# APM32F103VET6.net
KiCad netlist of a schematic drawn in Altium Designer
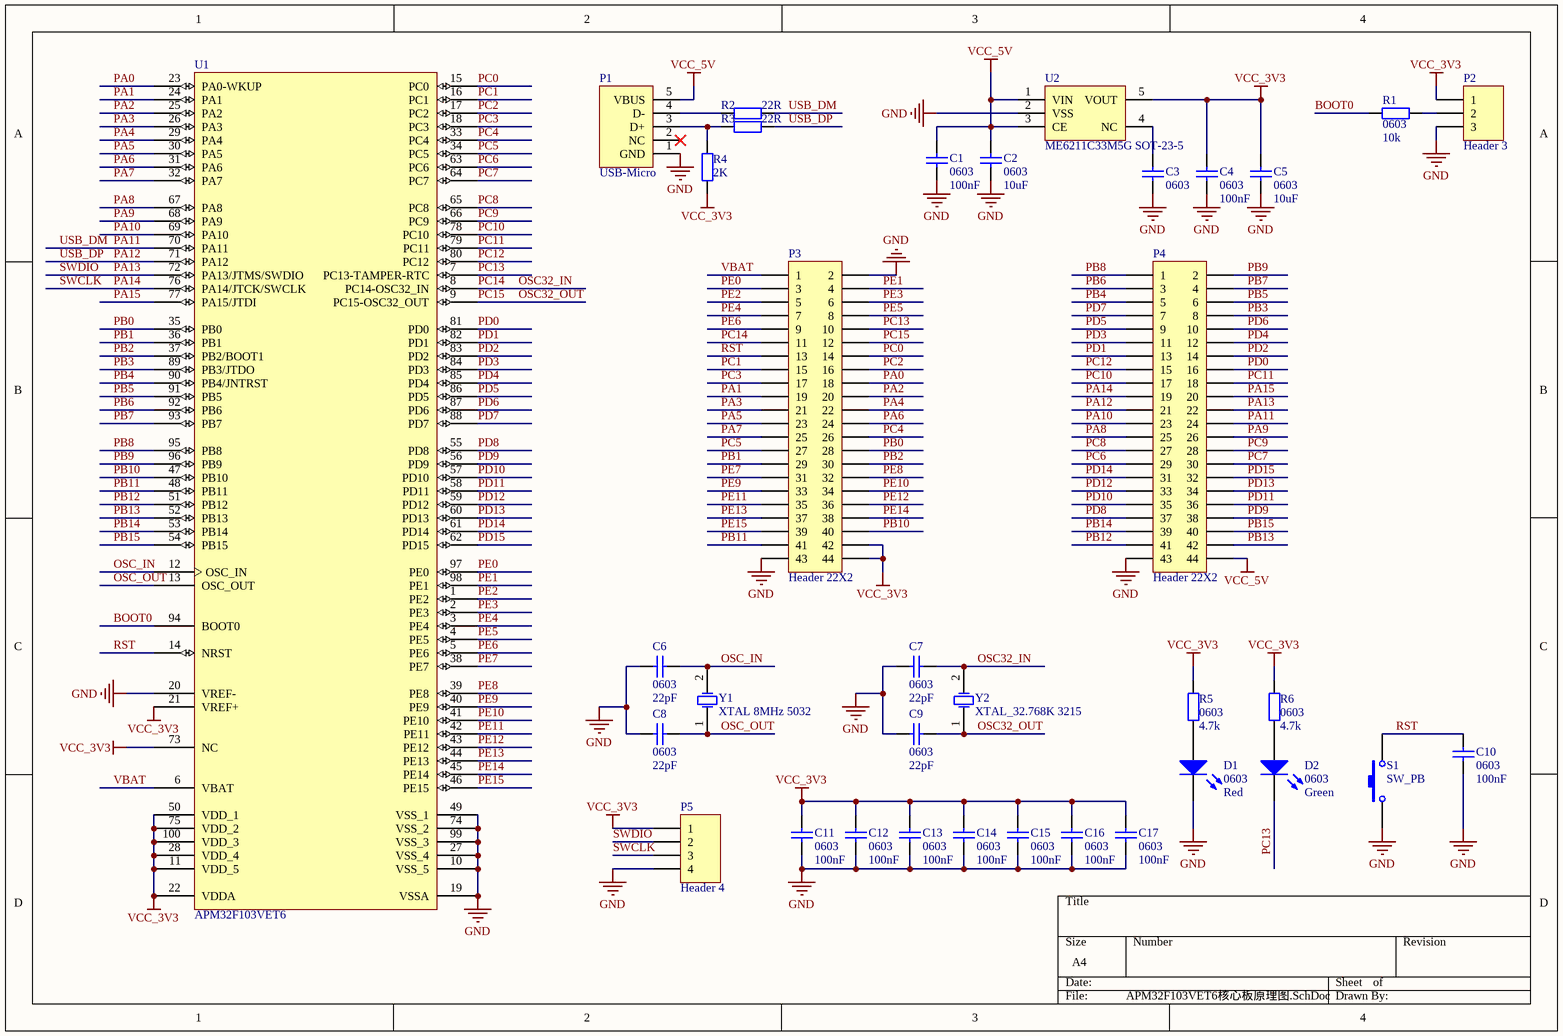
[diagram p0: APM32F103VET6核心板原理图.SchDoc]

(export (version "E")
  (design (tool "Eeschema 10.0.6"))
  (components
    (comp (ref "C1")
      (value "100nF")
      (footprint "0603")
      (description "Capacitor 0603")
      (fields (field (name "Comment") "Cap 0603"))
      (libsource (lib "Schlib1") (part "Cap 0603"))
    )
    (comp (ref "C2")
      (value "10uF")
      (footprint "0603")
      (description "Capacitor 0603")
      (fields (field (name "Comment") "Cap 0603"))
      (libsource (lib "Schlib1") (part "Cap 0603"))
    )
    (comp (ref "C3")
      (value "Cap 0603")
      (footprint "0603")
      (description "Capacitor 0603")
      (libsource (lib "Schlib1") (part "Cap 0603"))
    )
    (comp (ref "C4")
      (value "100nF")
      (footprint "0603")
      (description "Capacitor 0603")
      (fields (field (name "Comment") "Cap 0603"))
      (libsource (lib "Schlib1") (part "Cap 0603"))
    )
    (comp (ref "C5")
      (value "10uF")
      (footprint "0603")
      (description "Capacitor 0603")
      (fields (field (name "Comment") "Cap 0603"))
      (libsource (lib "Schlib1") (part "Cap 0603"))
    )
    (comp (ref "C6")
      (value "22pF")
      (footprint "0603")
      (description "Capacitor 0603")
      (fields (field (name "Comment") "Cap 0603"))
      (libsource (lib "Schlib1") (part "Cap 0603"))
    )
    (comp (ref "C7")
      (value "22pF")
      (footprint "0603")
      (description "Capacitor 0603")
      (fields (field (name "Comment") "Cap 0603"))
      (libsource (lib "Schlib1") (part "Cap 0603"))
    )
    (comp (ref "C8")
      (value "22pF")
      (footprint "0603")
      (description "Capacitor 0603")
      (fields (field (name "Comment") "Cap 0603"))
      (libsource (lib "Schlib1") (part "Cap 0603"))
    )
    (comp (ref "C9")
      (value "22pF")
      (footprint "0603")
      (description "Capacitor 0603")
      (fields (field (name "Comment") "Cap 0603"))
      (libsource (lib "Schlib1") (part "Cap 0603"))
    )
    (comp (ref "C10")
      (value "100nF")
      (footprint "0603")
      (description "Capacitor 0603")
      (fields (field (name "Comment") "Cap 0603"))
      (libsource (lib "Schlib1") (part "Cap 0603"))
    )
    (comp (ref "C11")
      (value "100nF")
      (footprint "0603")
      (description "Capacitor 0603")
      (fields (field (name "Comment") "Cap 0603"))
      (libsource (lib "Schlib1") (part "Cap 0603"))
    )
    (comp (ref "C12")
      (value "100nF")
      (footprint "0603")
      (description "Capacitor 0603")
      (fields (field (name "Comment") "Cap 0603"))
      (libsource (lib "Schlib1") (part "Cap 0603"))
    )
    (comp (ref "C13")
      (value "100nF")
      (footprint "0603")
      (description "Capacitor 0603")
      (fields (field (name "Comment") "Cap 0603"))
      (libsource (lib "Schlib1") (part "Cap 0603"))
    )
    (comp (ref "C14")
      (value "100nF")
      (footprint "0603")
      (description "Capacitor 0603")
      (fields (field (name "Comment") "Cap 0603"))
      (libsource (lib "Schlib1") (part "Cap 0603"))
    )
    (comp (ref "C15")
      (value "100nF")
      (footprint "0603")
      (description "Capacitor 0603")
      (fields (field (name "Comment") "Cap 0603"))
      (libsource (lib "Schlib1") (part "Cap 0603"))
    )
    (comp (ref "C16")
      (value "100nF")
      (footprint "0603")
      (description "Capacitor 0603")
      (fields (field (name "Comment") "Cap 0603"))
      (libsource (lib "Schlib1") (part "Cap 0603"))
    )
    (comp (ref "C17")
      (value "100nF")
      (footprint "0603")
      (description "Capacitor 0603")
      (fields (field (name "Comment") "Cap 0603"))
      (libsource (lib "Schlib1") (part "Cap 0603"))
    )
    (comp (ref "D1")
      (value "Red")
      (footprint "0603")
      (description "LED 0603")
      (libsource (lib "Schlib1") (part "LED 0603"))
    )
    (comp (ref "D2")
      (value "Green")
      (footprint "0603")
      (description "LED 0603")
      (libsource (lib "Schlib1") (part "LED 0603"))
    )
    (comp (ref "P1")
      (value "USB-Micro")
      (footprint "USB Micro")
      (libsource (lib "Schlib1") (part "USB-Micro"))
    )
    (comp (ref "P2")
      (value "Header 3")
      (footprint "HDR1X3")
      (description "Header, 3-Pin")
      (fields (field (name "PUBLISHER") "Altium Limited"))
      (libsource (lib "Miscellaneous Connectors") (part "Header 3"))
    )
    (comp (ref "P3")
      (value "Header 22X2")
      (footprint "HDR2X22")
      (description "Header, 22-Pin, Dual row")
      (fields (field (name "PUBLISHER") "Altium Limited"))
      (libsource (lib "Miscellaneous Connectors") (part "Header 22X2"))
    )
    (comp (ref "P4")
      (value "Header 22X2")
      (footprint "HDR2X22")
      (description "Header, 22-Pin, Dual row")
      (fields (field (name "PUBLISHER") "Altium Limited"))
      (libsource (lib "Miscellaneous Connectors") (part "Header 22X2"))
    )
    (comp (ref "P5")
      (value "Header 4")
      (footprint "HDR1X4")
      (description "Header, 4-Pin")
      (fields (field (name "PUBLISHER") "Altium Limited"))
      (libsource (lib "Miscellaneous Connectors") (part "Header 4"))
    )
    (comp (ref "R1")
      (value "10k")
      (footprint "0603")
      (description "Resistor 0603")
      (fields (field (name "Comment") "Res 0603"))
      (libsource (lib "") (part "Res 0603_1"))
    )
    (comp (ref "R2")
      (value "22R")
      (footprint "R0603-R/C-BY")
      (description "Resistor 0603")
      (fields (field (name "Comment") "Res 0603"))
      (libsource (lib "") (part "Res 0603_1"))
    )
    (comp (ref "R3")
      (value "22R")
      (footprint "R0603-R/C-BY")
      (description "Resistor 0603")
      (fields (field (name "Comment") "Res 0603"))
      (libsource (lib "") (part "Res 0603_1"))
    )
    (comp (ref "R4")
      (value "2K")
      (footprint "R0603-R/C-BY")
      (description "Resistor 0603")
      (fields (field (name "Comment") "Res 0603"))
      (libsource (lib "") (part "Res 0603_2"))
    )
    (comp (ref "R5")
      (value "4.7k")
      (footprint "0603")
      (description "Resistor 0603")
      (fields (field (name "Comment") "Res 0603"))
      (libsource (lib "Schlib1") (part "Res 0603"))
    )
    (comp (ref "R6")
      (value "4.7k")
      (footprint "0603")
      (description "Resistor 0603")
      (fields (field (name "Comment") "Res 0603"))
      (libsource (lib "Schlib1") (part "Res 0603"))
    )
    (comp (ref "S1") (value "SW_PB") (footprint "SW-2Pin") (libsource (lib "Schlib1") (part "SW_PB")))
    (comp (ref "U1")
      (value "APM32F103VET6")
      (footprint "LQFP100_M")
      (description "STM32 ARM-based 32-bit MCU with 64 Kbytes Flash, 100-pin LQFP, Industrial Temperature")
      (fields (field (name "PUBLISHER") "Altium Limited"))
      (libsource (lib "ST Microcontroller 32-Bit STM32") (part "STM32F103VBT6"))
    )
    (comp (ref "U2")
      (value "ME6211C33M5G SOT-23-5")
      (footprint "SOT-23-5")
      (libsource (lib "Schlib1") (part "ME6211C33M5G"))
    )
    (comp (ref "Y1")
      (value "XTAL 8MHz 5032")
      (footprint "XTAL 5032")
      (description "XTAL 8MHZ")
      (libsource (lib "Schlib1") (part "XTAL 8MHZ"))
    )
    (comp (ref "Y2")
      (value "XTAL_32.768K 3215")
      (footprint "XTAL 3215")
      (libsource (lib "Schlib1") (part "XTAL_32.768K 3215"))
    )
  )
  (nets
    (net (code "1") (name "/BOOT0") (class "Default")
      (node (ref "R1") (pin "1") (pinfunction "1_1") (pintype "passive"))
      (node (ref "U1") (pin "94") (pinfunction "BOOT0_94") (pintype "passive"))
    )
    (net (code "2") (name "/OSC32_IN") (class "Default")
      (node (ref "C7") (pin "1") (pinfunction "1_1") (pintype "passive"))
      (node (ref "P3") (pin "11") (pinfunction "11_11") (pintype "passive"))
      (node (ref "U1") (pin "8") (pinfunction "PC14-OSC32_IN_8") (pintype "bidirectional"))
      (node (ref "Y2") (pin "2") (pinfunction "OSC2_2") (pintype "passive"))
    )
    (net (code "3") (name "/OSC32_OUT") (class "Default")
      (node (ref "C9") (pin "1") (pinfunction "1_1") (pintype "passive"))
      (node (ref "P3") (pin "12") (pinfunction "12_12") (pintype "passive"))
      (node (ref "U1") (pin "9") (pinfunction "PC15-OSC32_OUT_9") (pintype "bidirectional"))
      (node (ref "Y2") (pin "1") (pinfunction "OSC1_1") (pintype "passive"))
    )
    (net (code "4") (name "/OSC_IN") (class "Default")
      (node (ref "C6") (pin "1") (pinfunction "1_1") (pintype "passive"))
      (node (ref "U1") (pin "12") (pinfunction "OSC_IN_12") (pintype "passive"))
      (node (ref "Y1") (pin "2") (pinfunction "OSC2_2") (pintype "passive"))
    )
    (net (code "5") (name "/OSC_OUT") (class "Default")
      (node (ref "C8") (pin "1") (pinfunction "1_1") (pintype "passive"))
      (node (ref "U1") (pin "13") (pinfunction "OSC_OUT_13") (pintype "passive"))
      (node (ref "Y1") (pin "1") (pinfunction "OSC1_1") (pintype "passive"))
    )
    (net (code "6") (name "/PA0") (class "Default")
      (node (ref "P3") (pin "18") (pinfunction "18_18") (pintype "passive"))
      (node (ref "U1") (pin "23") (pinfunction "PA0-WKUP_23") (pintype "bidirectional"))
    )
    (net (code "7") (name "/PA1") (class "Default")
      (node (ref "P3") (pin "19") (pinfunction "19_19") (pintype "passive"))
      (node (ref "U1") (pin "24") (pinfunction "PA1_24") (pintype "bidirectional"))
    )
    (net (code "8") (name "/PA2") (class "Default")
      (node (ref "P3") (pin "20") (pinfunction "20_20") (pintype "passive"))
      (node (ref "U1") (pin "25") (pinfunction "PA2_25") (pintype "bidirectional"))
    )
    (net (code "9") (name "/PA3") (class "Default")
      (node (ref "P3") (pin "21") (pinfunction "21_21") (pintype "passive"))
      (node (ref "U1") (pin "26") (pinfunction "PA3_26") (pintype "bidirectional"))
    )
    (net (code "10") (name "/PA4") (class "Default")
      (node (ref "P3") (pin "22") (pinfunction "22_22") (pintype "passive"))
      (node (ref "U1") (pin "29") (pinfunction "PA4_29") (pintype "bidirectional"))
    )
    (net (code "11") (name "/PA5") (class "Default")
      (node (ref "P3") (pin "23") (pinfunction "23_23") (pintype "passive"))
      (node (ref "U1") (pin "30") (pinfunction "PA5_30") (pintype "bidirectional"))
    )
    (net (code "12") (name "/PA6") (class "Default")
      (node (ref "P3") (pin "24") (pinfunction "24_24") (pintype "passive"))
      (node (ref "U1") (pin "31") (pinfunction "PA6_31") (pintype "bidirectional"))
    )
    (net (code "13") (name "/PA7") (class "Default")
      (node (ref "P3") (pin "25") (pinfunction "25_25") (pintype "passive"))
      (node (ref "U1") (pin "32") (pinfunction "PA7_32") (pintype "bidirectional"))
    )
    (net (code "14") (name "/PA8") (class "Default")
      (node (ref "P4") (pin "25") (pinfunction "25_25") (pintype "passive"))
      (node (ref "U1") (pin "67") (pinfunction "PA8_67") (pintype "bidirectional"))
    )
    (net (code "15") (name "/PA9") (class "Default")
      (node (ref "P4") (pin "26") (pinfunction "26_26") (pintype "passive"))
      (node (ref "U1") (pin "68") (pinfunction "PA9_68") (pintype "bidirectional"))
    )
    (net (code "16") (name "/PA10") (class "Default")
      (node (ref "P4") (pin "23") (pinfunction "23_23") (pintype "passive"))
      (node (ref "U1") (pin "69") (pinfunction "PA10_69") (pintype "bidirectional"))
    )
    (net (code "17") (name "/PA11") (class "Default")
      (node (ref "P4") (pin "24") (pinfunction "24_24") (pintype "passive"))
      (node (ref "R2") (pin "2") (pinfunction "2_2") (pintype "passive"))
      (node (ref "U1") (pin "70") (pinfunction "PA11_70") (pintype "bidirectional"))
    )
    (net (code "18") (name "/PA12") (class "Default")
      (node (ref "P4") (pin "21") (pinfunction "21_21") (pintype "passive"))
      (node (ref "R3") (pin "2") (pinfunction "2_2") (pintype "passive"))
      (node (ref "U1") (pin "71") (pinfunction "PA12_71") (pintype "bidirectional"))
    )
    (net (code "19") (name "/PA13") (class "Default")
      (node (ref "P4") (pin "22") (pinfunction "22_22") (pintype "passive"))
      (node (ref "P5") (pin "2") (pinfunction "2_2") (pintype "passive"))
      (node (ref "U1") (pin "72") (pinfunction "PA13/JTMS/SWDIO_72") (pintype "bidirectional"))
    )
    (net (code "20") (name "/PA14") (class "Default")
      (node (ref "P4") (pin "19") (pinfunction "19_19") (pintype "passive"))
      (node (ref "P5") (pin "3") (pinfunction "3_3") (pintype "passive"))
      (node (ref "U1") (pin "76") (pinfunction "PA14/JTCK/SWCLK_76") (pintype "bidirectional"))
    )
    (net (code "21") (name "/PA15") (class "Default")
      (node (ref "P4") (pin "20") (pinfunction "20_20") (pintype "passive"))
      (node (ref "U1") (pin "77") (pinfunction "PA15/JTDI_77") (pintype "bidirectional"))
    )
    (net (code "22") (name "/PB0") (class "Default")
      (node (ref "P3") (pin "28") (pinfunction "28_28") (pintype "passive"))
      (node (ref "U1") (pin "35") (pinfunction "PB0_35") (pintype "bidirectional"))
    )
    (net (code "23") (name "/PB1") (class "Default")
      (node (ref "P3") (pin "29") (pinfunction "29_29") (pintype "passive"))
      (node (ref "U1") (pin "36") (pinfunction "PB1_36") (pintype "bidirectional"))
    )
    (net (code "24") (name "/PB2") (class "Default")
      (node (ref "P3") (pin "30") (pinfunction "30_30") (pintype "passive"))
      (node (ref "U1") (pin "37") (pinfunction "PB2/BOOT1_37") (pintype "bidirectional"))
    )
    (net (code "25") (name "/PB3") (class "Default")
      (node (ref "P4") (pin "8") (pinfunction "8_8") (pintype "passive"))
      (node (ref "U1") (pin "89") (pinfunction "PB3/JTDO_89") (pintype "bidirectional"))
    )
    (net (code "26") (name "/PB4") (class "Default")
      (node (ref "P4") (pin "5") (pinfunction "5_5") (pintype "passive"))
      (node (ref "U1") (pin "90") (pinfunction "PB4/JNTRST_90") (pintype "bidirectional"))
    )
    (net (code "27") (name "/PB5") (class "Default")
      (node (ref "P4") (pin "6") (pinfunction "6_6") (pintype "passive"))
      (node (ref "U1") (pin "91") (pinfunction "PB5_91") (pintype "bidirectional"))
    )
    (net (code "28") (name "/PB6") (class "Default")
      (node (ref "P4") (pin "3") (pinfunction "3_3") (pintype "passive"))
      (node (ref "U1") (pin "92") (pinfunction "PB6_92") (pintype "bidirectional"))
    )
    (net (code "29") (name "/PB7") (class "Default")
      (node (ref "P4") (pin "4") (pinfunction "4_4") (pintype "passive"))
      (node (ref "U1") (pin "93") (pinfunction "PB7_93") (pintype "bidirectional"))
    )
    (net (code "30") (name "/PB8") (class "Default")
      (node (ref "P4") (pin "1") (pinfunction "1_1") (pintype "passive"))
      (node (ref "U1") (pin "95") (pinfunction "PB8_95") (pintype "bidirectional"))
    )
    (net (code "31") (name "/PB9") (class "Default")
      (node (ref "P4") (pin "2") (pinfunction "2_2") (pintype "passive"))
      (node (ref "U1") (pin "96") (pinfunction "PB9_96") (pintype "bidirectional"))
    )
    (net (code "32") (name "/PB10") (class "Default")
      (node (ref "P3") (pin "40") (pinfunction "40_40") (pintype "passive"))
      (node (ref "U1") (pin "47") (pinfunction "PB10_47") (pintype "bidirectional"))
    )
    (net (code "33") (name "/PB11") (class "Default")
      (node (ref "P3") (pin "41") (pinfunction "41_41") (pintype "passive"))
      (node (ref "U1") (pin "48") (pinfunction "PB11_48") (pintype "bidirectional"))
    )
    (net (code "34") (name "/PB12") (class "Default")
      (node (ref "P4") (pin "41") (pinfunction "41_41") (pintype "passive"))
      (node (ref "U1") (pin "51") (pinfunction "PB12_51") (pintype "bidirectional"))
    )
    (net (code "35") (name "/PB13") (class "Default")
      (node (ref "P4") (pin "42") (pinfunction "42_42") (pintype "passive"))
      (node (ref "U1") (pin "52") (pinfunction "PB13_52") (pintype "bidirectional"))
    )
    (net (code "36") (name "/PB14") (class "Default")
      (node (ref "P4") (pin "39") (pinfunction "39_39") (pintype "passive"))
      (node (ref "U1") (pin "53") (pinfunction "PB14_53") (pintype "bidirectional"))
    )
    (net (code "37") (name "/PB15") (class "Default")
      (node (ref "P4") (pin "40") (pinfunction "40_40") (pintype "passive"))
      (node (ref "U1") (pin "54") (pinfunction "PB15_54") (pintype "bidirectional"))
    )
    (net (code "38") (name "/PC0") (class "Default")
      (node (ref "P3") (pin "14") (pinfunction "14_14") (pintype "passive"))
      (node (ref "U1") (pin "15") (pinfunction "PC0_15") (pintype "bidirectional"))
    )
    (net (code "39") (name "/PC1") (class "Default")
      (node (ref "P3") (pin "15") (pinfunction "15_15") (pintype "passive"))
      (node (ref "U1") (pin "16") (pinfunction "PC1_16") (pintype "bidirectional"))
    )
    (net (code "40") (name "/PC2") (class "Default")
      (node (ref "P3") (pin "16") (pinfunction "16_16") (pintype "passive"))
      (node (ref "U1") (pin "17") (pinfunction "PC2_17") (pintype "bidirectional"))
    )
    (net (code "41") (name "/PC3") (class "Default")
      (node (ref "P3") (pin "17") (pinfunction "17_17") (pintype "passive"))
      (node (ref "U1") (pin "18") (pinfunction "PC3_18") (pintype "bidirectional"))
    )
    (net (code "42") (name "/PC4") (class "Default")
      (node (ref "P3") (pin "26") (pinfunction "26_26") (pintype "passive"))
      (node (ref "U1") (pin "33") (pinfunction "PC4_33") (pintype "bidirectional"))
    )
    (net (code "43") (name "/PC5") (class "Default")
      (node (ref "P3") (pin "27") (pinfunction "27_27") (pintype "passive"))
      (node (ref "U1") (pin "34") (pinfunction "PC5_34") (pintype "bidirectional"))
    )
    (net (code "44") (name "/PC6") (class "Default")
      (node (ref "P4") (pin "29") (pinfunction "29_29") (pintype "passive"))
      (node (ref "U1") (pin "63") (pinfunction "PC6_63") (pintype "bidirectional"))
    )
    (net (code "45") (name "/PC7") (class "Default")
      (node (ref "P4") (pin "30") (pinfunction "30_30") (pintype "passive"))
      (node (ref "U1") (pin "64") (pinfunction "PC7_64") (pintype "bidirectional"))
    )
    (net (code "46") (name "/PC8") (class "Default")
      (node (ref "P4") (pin "27") (pinfunction "27_27") (pintype "passive"))
      (node (ref "U1") (pin "65") (pinfunction "PC8_65") (pintype "bidirectional"))
    )
    (net (code "47") (name "/PC9") (class "Default")
      (node (ref "P4") (pin "28") (pinfunction "28_28") (pintype "passive"))
      (node (ref "U1") (pin "66") (pinfunction "PC9_66") (pintype "bidirectional"))
    )
    (net (code "48") (name "/PC10") (class "Default")
      (node (ref "P4") (pin "17") (pinfunction "17_17") (pintype "passive"))
      (node (ref "U1") (pin "78") (pinfunction "PC10_78") (pintype "bidirectional"))
    )
    (net (code "49") (name "/PC11") (class "Default")
      (node (ref "P4") (pin "18") (pinfunction "18_18") (pintype "passive"))
      (node (ref "U1") (pin "79") (pinfunction "PC11_79") (pintype "bidirectional"))
    )
    (net (code "50") (name "/PC12") (class "Default")
      (node (ref "P4") (pin "15") (pinfunction "15_15") (pintype "passive"))
      (node (ref "U1") (pin "80") (pinfunction "PC12_80") (pintype "bidirectional"))
    )
    (net (code "51") (name "/PC13") (class "Default")
      (node (ref "D2") (pin "2") (pinfunction "K_2") (pintype "passive"))
      (node (ref "P3") (pin "10") (pinfunction "10_10") (pintype "passive"))
      (node (ref "U1") (pin "7") (pinfunction "PC13-TAMPER-RTC_7") (pintype "bidirectional"))
    )
    (net (code "52") (name "/PD0") (class "Default")
      (node (ref "P4") (pin "16") (pinfunction "16_16") (pintype "passive"))
      (node (ref "U1") (pin "81") (pinfunction "PD0_81") (pintype "bidirectional"))
    )
    (net (code "53") (name "/PD1") (class "Default")
      (node (ref "P4") (pin "13") (pinfunction "13_13") (pintype "passive"))
      (node (ref "U1") (pin "82") (pinfunction "PD1_82") (pintype "bidirectional"))
    )
    (net (code "54") (name "/PD2") (class "Default")
      (node (ref "P4") (pin "14") (pinfunction "14_14") (pintype "passive"))
      (node (ref "U1") (pin "83") (pinfunction "PD2_83") (pintype "bidirectional"))
    )
    (net (code "55") (name "/PD3") (class "Default")
      (node (ref "P4") (pin "11") (pinfunction "11_11") (pintype "passive"))
      (node (ref "U1") (pin "84") (pinfunction "PD3_84") (pintype "bidirectional"))
    )
    (net (code "56") (name "/PD4") (class "Default")
      (node (ref "P4") (pin "12") (pinfunction "12_12") (pintype "passive"))
      (node (ref "U1") (pin "85") (pinfunction "PD4_85") (pintype "bidirectional"))
    )
    (net (code "57") (name "/PD5") (class "Default")
      (node (ref "P4") (pin "9") (pinfunction "9_9") (pintype "passive"))
      (node (ref "U1") (pin "86") (pinfunction "PD5_86") (pintype "bidirectional"))
    )
    (net (code "58") (name "/PD6") (class "Default")
      (node (ref "P4") (pin "10") (pinfunction "10_10") (pintype "passive"))
      (node (ref "U1") (pin "87") (pinfunction "PD6_87") (pintype "bidirectional"))
    )
    (net (code "59") (name "/PD7") (class "Default")
      (node (ref "P4") (pin "7") (pinfunction "7_7") (pintype "passive"))
      (node (ref "U1") (pin "88") (pinfunction "PD7_88") (pintype "bidirectional"))
    )
    (net (code "60") (name "/PD8") (class "Default")
      (node (ref "P4") (pin "37") (pinfunction "37_37") (pintype "passive"))
      (node (ref "U1") (pin "55") (pinfunction "PD8_55") (pintype "bidirectional"))
    )
    (net (code "61") (name "/PD9") (class "Default")
      (node (ref "P4") (pin "38") (pinfunction "38_38") (pintype "passive"))
      (node (ref "U1") (pin "56") (pinfunction "PD9_56") (pintype "bidirectional"))
    )
    (net (code "62") (name "/PD10") (class "Default")
      (node (ref "P4") (pin "35") (pinfunction "35_35") (pintype "passive"))
      (node (ref "U1") (pin "57") (pinfunction "PD10_57") (pintype "bidirectional"))
    )
    (net (code "63") (name "/PD11") (class "Default")
      (node (ref "P4") (pin "36") (pinfunction "36_36") (pintype "passive"))
      (node (ref "U1") (pin "58") (pinfunction "PD11_58") (pintype "bidirectional"))
    )
    (net (code "64") (name "/PD12") (class "Default")
      (node (ref "P4") (pin "33") (pinfunction "33_33") (pintype "passive"))
      (node (ref "U1") (pin "59") (pinfunction "PD12_59") (pintype "bidirectional"))
    )
    (net (code "65") (name "/PD13") (class "Default")
      (node (ref "P4") (pin "34") (pinfunction "34_34") (pintype "passive"))
      (node (ref "U1") (pin "60") (pinfunction "PD13_60") (pintype "bidirectional"))
    )
    (net (code "66") (name "/PD14") (class "Default")
      (node (ref "P4") (pin "31") (pinfunction "31_31") (pintype "passive"))
      (node (ref "U1") (pin "61") (pinfunction "PD14_61") (pintype "bidirectional"))
    )
    (net (code "67") (name "/PD15") (class "Default")
      (node (ref "P4") (pin "32") (pinfunction "32_32") (pintype "passive"))
      (node (ref "U1") (pin "62") (pinfunction "PD15_62") (pintype "bidirectional"))
    )
    (net (code "68") (name "/PE0") (class "Default")
      (node (ref "P3") (pin "3") (pinfunction "3_3") (pintype "passive"))
      (node (ref "U1") (pin "97") (pinfunction "PE0_97") (pintype "bidirectional"))
    )
    (net (code "69") (name "/PE1") (class "Default")
      (node (ref "P3") (pin "4") (pinfunction "4_4") (pintype "passive"))
      (node (ref "U1") (pin "98") (pinfunction "PE1_98") (pintype "bidirectional"))
    )
    (net (code "70") (name "/PE2") (class "Default")
      (node (ref "P3") (pin "5") (pinfunction "5_5") (pintype "passive"))
      (node (ref "U1") (pin "1") (pinfunction "PE2_1") (pintype "bidirectional"))
    )
    (net (code "71") (name "/PE3") (class "Default")
      (node (ref "P3") (pin "6") (pinfunction "6_6") (pintype "passive"))
      (node (ref "U1") (pin "2") (pinfunction "PE3_2") (pintype "bidirectional"))
    )
    (net (code "72") (name "/PE4") (class "Default")
      (node (ref "P3") (pin "7") (pinfunction "7_7") (pintype "passive"))
      (node (ref "U1") (pin "3") (pinfunction "PE4_3") (pintype "bidirectional"))
    )
    (net (code "73") (name "/PE5") (class "Default")
      (node (ref "P3") (pin "8") (pinfunction "8_8") (pintype "passive"))
      (node (ref "U1") (pin "4") (pinfunction "PE5_4") (pintype "bidirectional"))
    )
    (net (code "74") (name "/PE6") (class "Default")
      (node (ref "P3") (pin "9") (pinfunction "9_9") (pintype "passive"))
      (node (ref "U1") (pin "5") (pinfunction "PE6_5") (pintype "bidirectional"))
    )
    (net (code "75") (name "/PE7") (class "Default")
      (node (ref "P3") (pin "31") (pinfunction "31_31") (pintype "passive"))
      (node (ref "U1") (pin "38") (pinfunction "PE7_38") (pintype "bidirectional"))
    )
    (net (code "76") (name "/PE8") (class "Default")
      (node (ref "P3") (pin "32") (pinfunction "32_32") (pintype "passive"))
      (node (ref "U1") (pin "39") (pinfunction "PE8_39") (pintype "bidirectional"))
    )
    (net (code "77") (name "/PE9") (class "Default")
      (node (ref "P3") (pin "33") (pinfunction "33_33") (pintype "passive"))
      (node (ref "U1") (pin "40") (pinfunction "PE9_40") (pintype "bidirectional"))
    )
    (net (code "78") (name "/PE10") (class "Default")
      (node (ref "P3") (pin "34") (pinfunction "34_34") (pintype "passive"))
      (node (ref "U1") (pin "41") (pinfunction "PE10_41") (pintype "bidirectional"))
    )
    (net (code "79") (name "/PE11") (class "Default")
      (node (ref "P3") (pin "35") (pinfunction "35_35") (pintype "passive"))
      (node (ref "U1") (pin "42") (pinfunction "PE11_42") (pintype "bidirectional"))
    )
    (net (code "80") (name "/PE12") (class "Default")
      (node (ref "P3") (pin "36") (pinfunction "36_36") (pintype "passive"))
      (node (ref "U1") (pin "43") (pinfunction "PE12_43") (pintype "bidirectional"))
    )
    (net (code "81") (name "/PE13") (class "Default")
      (node (ref "P3") (pin "37") (pinfunction "37_37") (pintype "passive"))
      (node (ref "U1") (pin "44") (pinfunction "PE13_44") (pintype "bidirectional"))
    )
    (net (code "82") (name "/PE14") (class "Default")
      (node (ref "P3") (pin "38") (pinfunction "38_38") (pintype "passive"))
      (node (ref "U1") (pin "45") (pinfunction "PE14_45") (pintype "bidirectional"))
    )
    (net (code "83") (name "/PE15") (class "Default")
      (node (ref "P3") (pin "39") (pinfunction "39_39") (pintype "passive"))
      (node (ref "U1") (pin "46") (pinfunction "PE15_46") (pintype "bidirectional"))
    )
    (net (code "84") (name "/RST") (class "Default")
      (node (ref "C10") (pin "2") (pinfunction "2_2") (pintype "passive"))
      (node (ref "P3") (pin "13") (pinfunction "13_13") (pintype "passive"))
      (node (ref "S1") (pin "2") (pinfunction "2_2") (pintype "passive"))
      (node (ref "U1") (pin "14") (pinfunction "NRST_14") (pintype "bidirectional"))
    )
    (net (code "85") (name "/VBAT") (class "Default")
      (node (ref "P3") (pin "1") (pinfunction "1_1") (pintype "passive"))
      (node (ref "U1") (pin "6") (pinfunction "VBAT_6") (pintype "power_in"))
    )
    (net (code "86") (name "GND") (class "Default")
      (node (ref "C1") (pin "1") (pinfunction "1_1") (pintype "passive"))
      (node (ref "C10") (pin "1") (pinfunction "1_1") (pintype "passive"))
      (node (ref "C11") (pin "1") (pinfunction "1_1") (pintype "passive"))
      (node (ref "C12") (pin "1") (pinfunction "1_1") (pintype "passive"))
      (node (ref "C13") (pin "1") (pinfunction "1_1") (pintype "passive"))
      (node (ref "C14") (pin "1") (pinfunction "1_1") (pintype "passive"))
      (node (ref "C15") (pin "1") (pinfunction "1_1") (pintype "passive"))
      (node (ref "C16") (pin "1") (pinfunction "1_1") (pintype "passive"))
      (node (ref "C17") (pin "1") (pinfunction "1_1") (pintype "passive"))
      (node (ref "C2") (pin "1") (pinfunction "1_1") (pintype "passive"))
      (node (ref "C3") (pin "1") (pinfunction "1_1") (pintype "passive"))
      (node (ref "C4") (pin "1") (pinfunction "1_1") (pintype "passive"))
      (node (ref "C5") (pin "1") (pinfunction "1_1") (pintype "passive"))
      (node (ref "C6") (pin "2") (pinfunction "2_2") (pintype "passive"))
      (node (ref "C7") (pin "2") (pinfunction "2_2") (pintype "passive"))
      (node (ref "C8") (pin "2") (pinfunction "2_2") (pintype "passive"))
      (node (ref "C9") (pin "2") (pinfunction "2_2") (pintype "passive"))
      (node (ref "D1") (pin "2") (pinfunction "K_2") (pintype "passive"))
      (node (ref "P1") (pin "1") (pinfunction "GND_1") (pintype "power_in"))
      (node (ref "P2") (pin "3") (pinfunction "3_3") (pintype "passive"))
      (node (ref "P3") (pin "2") (pinfunction "2_2") (pintype "passive"))
      (node (ref "P3") (pin "43") (pinfunction "43_43") (pintype "passive"))
      (node (ref "P4") (pin "43") (pinfunction "43_43") (pintype "passive"))
      (node (ref "P5") (pin "4") (pinfunction "4_4") (pintype "passive"))
      (node (ref "S1") (pin "1") (pinfunction "1_1") (pintype "passive"))
      (node (ref "U1") (pin "10") (pinfunction "VSS_5_10") (pintype "power_in"))
      (node (ref "U1") (pin "19") (pinfunction "VSSA_19") (pintype "power_in"))
      (node (ref "U1") (pin "20") (pinfunction "VREF-_20") (pintype "power_in"))
      (node (ref "U1") (pin "27") (pinfunction "VSS_4_27") (pintype "power_in"))
      (node (ref "U1") (pin "49") (pinfunction "VSS_1_49") (pintype "power_in"))
      (node (ref "U1") (pin "74") (pinfunction "VSS_2_74") (pintype "power_in"))
      (node (ref "U1") (pin "99") (pinfunction "VSS_3_99") (pintype "power_in"))
      (node (ref "U2") (pin "2") (pinfunction "VSS_2") (pintype "power_in"))
    )
    (net (code "87") (name "Net-(D1-A)") (class "Default")
      (node (ref "D1") (pin "1") (pinfunction "A_1") (pintype "passive"))
      (node (ref "R5") (pin "2") (pinfunction "2_2") (pintype "passive"))
    )
    (net (code "88") (name "Net-(D2-A)") (class "Default")
      (node (ref "D2") (pin "1") (pinfunction "A_1") (pintype "passive"))
      (node (ref "R6") (pin "2") (pinfunction "2_2") (pintype "passive"))
    )
    (net (code "89") (name "Net-(P1-D+)") (class "Default")
      (node (ref "P1") (pin "3") (pinfunction "D+_3") (pintype "power_in"))
      (node (ref "R3") (pin "1") (pinfunction "1_1") (pintype "passive"))
      (node (ref "R4") (pin "2") (pinfunction "2_2") (pintype "passive"))
    )
    (net (code "90") (name "Net-(P1-D-)") (class "Default")
      (node (ref "P1") (pin "4") (pinfunction "D-_4") (pintype "power_in"))
      (node (ref "R2") (pin "1") (pinfunction "1_1") (pintype "passive"))
    )
    (net (code "91") (name "Net-(P2-Pad2)") (class "Default")
      (node (ref "P2") (pin "2") (pinfunction "2_2") (pintype "passive"))
      (node (ref "R1") (pin "2") (pinfunction "2_2") (pintype "passive"))
    )
    (net (code "92") (name "Net-(U2-NC)") (class "Default")
      (node (ref "C3") (pin "2") (pinfunction "2_2") (pintype "passive"))
      (node (ref "U2") (pin "4") (pinfunction "NC_4") (pintype "power_in"))
    )
    (net (code "93") (name "VCC_3V3") (class "Default")
      (node (ref "C11") (pin "2") (pinfunction "2_2") (pintype "passive"))
      (node (ref "C12") (pin "2") (pinfunction "2_2") (pintype "passive"))
      (node (ref "C13") (pin "2") (pinfunction "2_2") (pintype "passive"))
      (node (ref "C14") (pin "2") (pinfunction "2_2") (pintype "passive"))
      (node (ref "C15") (pin "2") (pinfunction "2_2") (pintype "passive"))
      (node (ref "C16") (pin "2") (pinfunction "2_2") (pintype "passive"))
      (node (ref "C17") (pin "2") (pinfunction "2_2") (pintype "passive"))
      (node (ref "C4") (pin "2") (pinfunction "2_2") (pintype "passive"))
      (node (ref "C5") (pin "2") (pinfunction "2_2") (pintype "passive"))
      (node (ref "P2") (pin "1") (pinfunction "1_1") (pintype "passive"))
      (node (ref "P3") (pin "42") (pinfunction "42_42") (pintype "passive"))
      (node (ref "P3") (pin "44") (pinfunction "44_44") (pintype "passive"))
      (node (ref "P5") (pin "1") (pinfunction "1_1") (pintype "passive"))
      (node (ref "R4") (pin "1") (pinfunction "1_1") (pintype "passive"))
      (node (ref "R5") (pin "1") (pinfunction "1_1") (pintype "passive"))
      (node (ref "R6") (pin "1") (pinfunction "1_1") (pintype "passive"))
      (node (ref "U1") (pin "100") (pinfunction "VDD_3_100") (pintype "power_in"))
      (node (ref "U1") (pin "11") (pinfunction "VDD_5_11") (pintype "power_in"))
      (node (ref "U1") (pin "21") (pinfunction "VREF+_21") (pintype "power_in"))
      (node (ref "U1") (pin "22") (pinfunction "VDDA_22") (pintype "power_in"))
      (node (ref "U1") (pin "28") (pinfunction "VDD_4_28") (pintype "power_in"))
      (node (ref "U1") (pin "50") (pinfunction "VDD_1_50") (pintype "power_in"))
      (node (ref "U1") (pin "73") (pinfunction "NC_73") (pintype "passive"))
      (node (ref "U1") (pin "75") (pinfunction "VDD_2_75") (pintype "power_in"))
      (node (ref "U2") (pin "5") (pinfunction "VOUT_5") (pintype "power_in"))
    )
    (net (code "94") (name "VCC_5V") (class "Default")
      (node (ref "C1") (pin "2") (pinfunction "2_2") (pintype "passive"))
      (node (ref "C2") (pin "2") (pinfunction "2_2") (pintype "passive"))
      (node (ref "P1") (pin "5") (pinfunction "VBUS_5") (pintype "power_in"))
      (node (ref "P4") (pin "44") (pinfunction "44_44") (pintype "passive"))
      (node (ref "U2") (pin "1") (pinfunction "VIN_1") (pintype "power_in"))
      (node (ref "U2") (pin "3") (pinfunction "CE_3") (pintype "power_in"))
    )
    (net (code "95") (name "unconnected-(P1-NC-Pad2)") (class "Default")
      (node (ref "P1") (pin "2") (pinfunction "NC_2") (pintype "power_in+no_connect"))
    )
  )
)
